# untitled.net
KiCad netlist of a schematic drawn in EAGLE
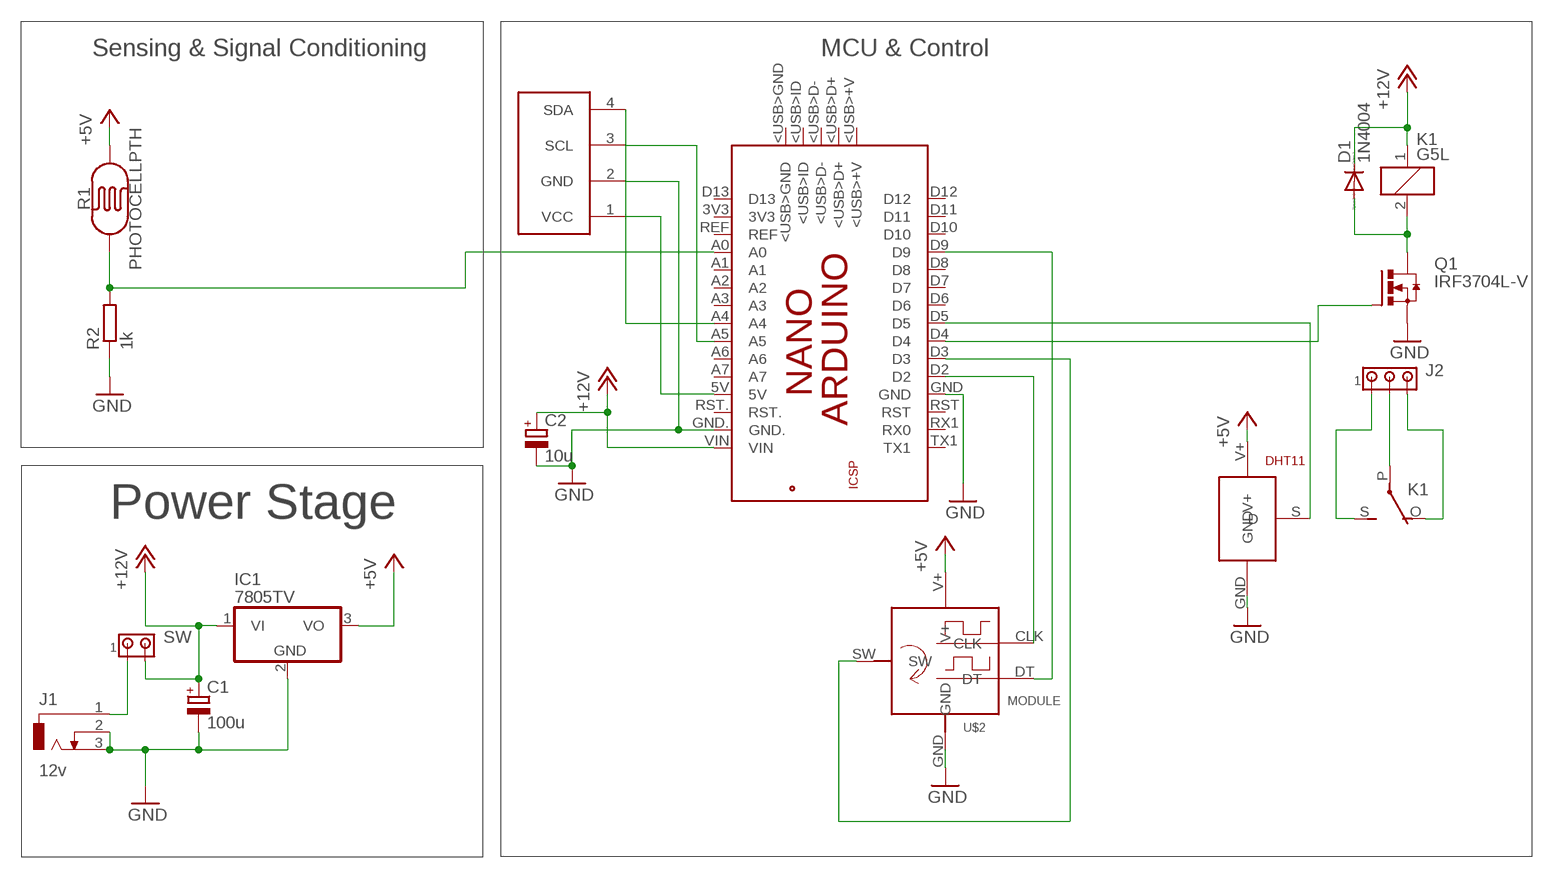
[diagram p0: schematic, sheet 1]

(export (version "E")
  (design (tool "Eeschema 10.0.6"))
  (components
    (comp (ref "C1")
      (value "100u")
      (footprint "eagle-import:E3,5-8")
      (libsource (lib "eagle-import") (part "CPOL-EUE3.5-8"))
    )
    (comp (ref "C2")
      (value "10u")
      (footprint "eagle-import:E3,5-8")
      (libsource (lib "eagle-import") (part "CPOL-EUE3.5-8"))
    )
    (comp (ref "D1")
      (value "1N4004")
      (footprint "eagle-import:DO41-10")
      (fields (field (name "SPICEPREFIX") "D"))
      (libsource (lib "eagle-import") (part "1N4004"))
    )
    (comp (ref "DHT11")
      (value "DHT11")
      (footprint "eagle-import:DHT11")
      (libsource (lib "eagle-import") (part "DHT11"))
    )
    (comp (ref "IC1")
      (value "7805TV")
      (footprint "eagle-import:TO220V")
      (libsource (lib "eagle-import") (part "78TV05"))
    )
    (comp (ref "J1")
      (value "12v")
      (footprint "eagle-import:DCJ0303")
      (libsource (lib "eagle-import") (part "DCJ0303"))
    )
    (comp (ref "J2")
      (value "MTA03-156")
      (footprint "eagle-import:1X3MTA")
      (libsource (lib "eagle-import") (part "MTA03-156"))
    )
    (comp (ref "K1")
      (value "G5L")
      (footprint "eagle-import:G5LE")
      (fields (field (name "SPICEPREFIX") "B"))
      (libsource (lib "eagle-import") (part "G5L"))
    )
    (comp (ref "PCB1")
      (value "ARDUINO_NANO")
      (footprint "eagle-import:ARDUINO_NANO")
      (libsource (lib "eagle-import") (part "ARDUINO_NANO"))
    )
    (comp (ref "Q1")
      (value "IRF3704L-V")
      (footprint "eagle-import:TO262-V")
      (fields (field (name "SPICEPREFIX") "Q"))
      (libsource (lib "eagle-import") (part "IRF3704L-V"))
    )
    (comp (ref "R1")
      (value "PHOTOCELLPTH")
      (footprint "eagle-import:PHOTOCELL")
      (libsource (lib "eagle-import") (part "PHOTOCELLPTH"))
    )
    (comp (ref "R2")
      (value "1k")
      (footprint "eagle-import:0207_7")
      (libsource (lib "eagle-import") (part "R-EU_0207/7"))
    )
    (comp (ref "SW")
      (value "MTA02-156")
      (footprint "eagle-import:1X2MTA")
      (libsource (lib "eagle-import") (part "MTA02-156"))
    )
    (comp (ref "U$1")
      (value "I2C_OLED")
      (footprint "eagle-import:I2C_OLED_PACKAGE")
      (libsource (lib "eagle-import") (part "I2C_OLED"))
    )
    (comp (ref "U$2")
      (value "MODULE")
      (footprint "eagle-import:MODULE_SHEILD")
      (libsource (lib "eagle-import") (part "MODULE"))
    )
  )
  (nets
    (net (code "1") (name "+5V") (class "Default")
      (node (ref "DHT11") (pin "V+") (pinfunction "V+_V+") (pintype "power_in"))
      (node (ref "IC1") (pin "3") (pinfunction "VO_3") (pintype "passive"))
      (node (ref "R1") (pin "2") (pinfunction "P$2_2") (pintype "bidirectional"))
      (node (ref "U$2") (pin "V+") (pinfunction "V+_V+") (pintype "power_in"))
    )
    (net (code "2") (name "+12V") (class "Default")
      (node (ref "C1") (pin "+") (pinfunction "+_+") (pintype "passive"))
      (node (ref "C2") (pin "+") (pinfunction "+_+") (pintype "passive"))
      (node (ref "D1") (pin "C") (pinfunction "C_C") (pintype "passive"))
      (node (ref "IC1") (pin "1") (pinfunction "VI_1") (pintype "input"))
      (node (ref "K1") (pin "1") (pinfunction "1_1") (pintype "passive"))
      (node (ref "PCB1") (pin "VIN") (pinfunction "VIN_VIN") (pintype "bidirectional"))
      (node (ref "SW") (pin "2") (pinfunction "2_2") (pintype "passive"))
    )
    (net (code "3") (name "GND") (class "Default")
      (node (ref "C1") (pin "-") (pinfunction "-_-") (pintype "passive"))
      (node (ref "C2") (pin "-") (pinfunction "-_-") (pintype "passive"))
      (node (ref "DHT11") (pin "GND") (pinfunction "GND_GND") (pintype "power_in"))
      (node (ref "IC1") (pin "2") (pinfunction "GND_2") (pintype "passive"))
      (node (ref "J1") (pin "2") (pinfunction "2_2") (pintype "passive"))
      (node (ref "J1") (pin "3") (pinfunction "3_3") (pintype "passive"))
      (node (ref "PCB1") (pin "GND") (pinfunction "GND_GND") (pintype "bidirectional"))
      (node (ref "PCB1") (pin "GND.") (pinfunction "GND._GND.") (pintype "bidirectional"))
      (node (ref "Q1") (pin "3") (pinfunction "S_3") (pintype "passive"))
      (node (ref "R2") (pin "1") (pinfunction "1_1") (pintype "passive"))
      (node (ref "U$1") (pin "2") (pinfunction "GND_2") (pintype "bidirectional"))
      (node (ref "U$2") (pin "GND") (pinfunction "GND_GND") (pintype "power_in"))
    )
    (net (code "4") (name "Net-(DHT11-D)") (class "Default")
      (node (ref "DHT11") (pin "S") (pinfunction "D_S") (pintype "bidirectional"))
      (node (ref "PCB1") (pin "D5") (pinfunction "D5_D5") (pintype "bidirectional"))
    )
    (net (code "5") (name "Net-(J1-Pad1)") (class "Default")
      (node (ref "J1") (pin "1") (pinfunction "1_1") (pintype "passive"))
      (node (ref "SW") (pin "1") (pinfunction "1_1") (pintype "passive"))
    )
    (net (code "6") (name "Net-(J2-Pad1)") (class "Default")
      (node (ref "J2") (pin "1") (pinfunction "1_1") (pintype "passive"))
      (node (ref "K1") (pin "S") (pinfunction "S_S") (pintype "passive"))
    )
    (net (code "7") (name "Net-(J2-Pad2)") (class "Default")
      (node (ref "J2") (pin "2") (pinfunction "2_2") (pintype "passive"))
      (node (ref "K1") (pin "P") (pinfunction "P_P") (pintype "passive"))
    )
    (net (code "8") (name "Net-(J2-Pad3)") (class "Default")
      (node (ref "J2") (pin "3") (pinfunction "3_3") (pintype "passive"))
      (node (ref "K1") (pin "O") (pinfunction "O_O") (pintype "passive"))
    )
    (net (code "9") (name "Net-(PCB1-PadD2)") (class "Default")
      (node (ref "PCB1") (pin "D2") (pinfunction "D2_D2") (pintype "bidirectional"))
      (node (ref "U$2") (pin "CLK") (pinfunction "CLK_CLK") (pintype "bidirectional"))
    )
    (net (code "10") (name "Net-(PCB1-PadD3)") (class "Default")
      (node (ref "PCB1") (pin "D3") (pinfunction "D3_D3") (pintype "bidirectional"))
      (node (ref "U$2") (pin "SW") (pinfunction "SW_SW") (pintype "bidirectional"))
    )
    (net (code "11") (name "Net-(PCB1-PadD9)") (class "Default")
      (node (ref "PCB1") (pin "D9") (pinfunction "D9_D9") (pintype "bidirectional"))
      (node (ref "U$2") (pin "DT") (pinfunction "DT_DT") (pintype "bidirectional"))
    )
    (net (code "12") (name "Net-(Q1-D)") (class "Default")
      (node (ref "D1") (pin "A") (pinfunction "A_A") (pintype "passive"))
      (node (ref "K1") (pin "2") (pinfunction "2_2") (pintype "passive"))
      (node (ref "Q1") (pin "2") (pinfunction "D_2") (pintype "passive"))
    )
    (net (code "13") (name "Net-(Q1-G)") (class "Default")
      (node (ref "PCB1") (pin "D4") (pinfunction "D4_D4") (pintype "bidirectional"))
      (node (ref "Q1") (pin "1") (pinfunction "G_1") (pintype "passive"))
    )
    (net (code "14") (name "Net-(R1-P$1)") (class "Default")
      (node (ref "PCB1") (pin "A0") (pinfunction "A0_A0") (pintype "bidirectional"))
      (node (ref "R1") (pin "1") (pinfunction "P$1_1") (pintype "bidirectional"))
      (node (ref "R2") (pin "2") (pinfunction "2_2") (pintype "passive"))
    )
    (net (code "15") (name "Net-(U$1-SCL)") (class "Default")
      (node (ref "PCB1") (pin "A5") (pinfunction "A5_A5") (pintype "bidirectional"))
      (node (ref "U$1") (pin "3") (pinfunction "SCL_3") (pintype "bidirectional"))
    )
    (net (code "16") (name "Net-(U$1-SDA)") (class "Default")
      (node (ref "PCB1") (pin "A4") (pinfunction "A4_A4") (pintype "bidirectional"))
      (node (ref "U$1") (pin "4") (pinfunction "SDA_4") (pintype "bidirectional"))
    )
    (net (code "17") (name "Net-(U$1-VCC)") (class "Default")
      (node (ref "PCB1") (pin "5V") (pinfunction "5V_5V") (pintype "bidirectional"))
      (node (ref "U$1") (pin "1") (pinfunction "VCC_1") (pintype "bidirectional"))
    )
    (net (code "18") (name "unconnected-(PCB1-Pad3V3)") (class "Default")
      (node (ref "PCB1") (pin "3V3") (pinfunction "3V3_3V3") (pintype "bidirectional"))
    )
    (net (code "19") (name "unconnected-(PCB1-Pad5V.)") (class "Default")
      (node (ref "PCB1") (pin "5V.") (pinfunction "5V._5V.") (pintype "bidirectional"))
    )
    (net (code "20") (name "unconnected-(PCB1-Pad<USB>+V)") (class "Default")
      (node (ref "PCB1") (pin "<USB>+V") (pinfunction "<USB>+V_<USB>+V") (pintype "bidirectional"))
    )
    (net (code "21") (name "unconnected-(PCB1-Pad<USB>D+)") (class "Default")
      (node (ref "PCB1") (pin "<USB>D+") (pinfunction "<USB>D+_<USB>D+") (pintype "bidirectional"))
    )
    (net (code "22") (name "unconnected-(PCB1-Pad<USB>D-)") (class "Default")
      (node (ref "PCB1") (pin "<USB>D-") (pinfunction "<USB>D-_<USB>D-") (pintype "bidirectional"))
    )
    (net (code "23") (name "unconnected-(PCB1-Pad<USB>GND)") (class "Default")
      (node (ref "PCB1") (pin "<USB>GND") (pinfunction "<USB>GND_<USB>GND") (pintype "bidirectional"))
    )
    (net (code "24") (name "unconnected-(PCB1-Pad<USB>ID)") (class "Default")
      (node (ref "PCB1") (pin "<USB>ID") (pinfunction "<USB>ID_<USB>ID") (pintype "bidirectional"))
    )
    (net (code "25") (name "unconnected-(PCB1-PadA1)") (class "Default")
      (node (ref "PCB1") (pin "A1") (pinfunction "A1_A1") (pintype "bidirectional"))
    )
    (net (code "26") (name "unconnected-(PCB1-PadA2)") (class "Default")
      (node (ref "PCB1") (pin "A2") (pinfunction "A2_A2") (pintype "bidirectional"))
    )
    (net (code "27") (name "unconnected-(PCB1-PadA3)") (class "Default")
      (node (ref "PCB1") (pin "A3") (pinfunction "A3_A3") (pintype "bidirectional"))
    )
    (net (code "28") (name "unconnected-(PCB1-PadA6)") (class "Default")
      (node (ref "PCB1") (pin "A6") (pinfunction "A6_A6") (pintype "bidirectional"))
    )
    (net (code "29") (name "unconnected-(PCB1-PadA7)") (class "Default")
      (node (ref "PCB1") (pin "A7") (pinfunction "A7_A7") (pintype "bidirectional"))
    )
    (net (code "30") (name "unconnected-(PCB1-PadD6)") (class "Default")
      (node (ref "PCB1") (pin "D6") (pinfunction "D6_D6") (pintype "bidirectional"))
    )
    (net (code "31") (name "unconnected-(PCB1-PadD7)") (class "Default")
      (node (ref "PCB1") (pin "D7") (pinfunction "D7_D7") (pintype "bidirectional"))
    )
    (net (code "32") (name "unconnected-(PCB1-PadD8)") (class "Default")
      (node (ref "PCB1") (pin "D8") (pinfunction "D8_D8") (pintype "bidirectional"))
    )
    (net (code "33") (name "unconnected-(PCB1-PadD10)") (class "Default")
      (node (ref "PCB1") (pin "D10") (pinfunction "D10_D10") (pintype "bidirectional"))
    )
    (net (code "34") (name "unconnected-(PCB1-PadD11)") (class "Default")
      (node (ref "PCB1") (pin "D11") (pinfunction "D11_D11") (pintype "bidirectional"))
    )
    (net (code "35") (name "unconnected-(PCB1-PadD12)") (class "Default")
      (node (ref "PCB1") (pin "D12") (pinfunction "D12_D12") (pintype "bidirectional"))
    )
    (net (code "36") (name "unconnected-(PCB1-PadD13)") (class "Default")
      (node (ref "PCB1") (pin "D13") (pinfunction "D13_D13") (pintype "bidirectional"))
    )
    (net (code "37") (name "unconnected-(PCB1-PadGND_)") (class "Default")
      (node (ref "PCB1") (pin "GND_") (pinfunction "GND__GND_") (pintype "bidirectional"))
    )
    (net (code "38") (name "unconnected-(PCB1-PadMISO)") (class "Default")
      (node (ref "PCB1") (pin "MISO") (pinfunction "MISO_MISO") (pintype "bidirectional"))
    )
    (net (code "39") (name "unconnected-(PCB1-PadMOSI)") (class "Default")
      (node (ref "PCB1") (pin "MOSI") (pinfunction "MOSI_MOSI") (pintype "bidirectional"))
    )
    (net (code "40") (name "unconnected-(PCB1-PadREF)") (class "Default")
      (node (ref "PCB1") (pin "REF") (pinfunction "REF_REF") (pintype "bidirectional"))
    )
    (net (code "41") (name "unconnected-(PCB1-PadRESET..)") (class "Default")
      (node (ref "PCB1") (pin "RESET..") (pinfunction "RESET.._RESET..") (pintype "bidirectional"))
    )
    (net (code "42") (name "unconnected-(PCB1-PadRST)") (class "Default")
      (node (ref "PCB1") (pin "RST") (pinfunction "RST_RST") (pintype "bidirectional"))
    )
    (net (code "43") (name "unconnected-(PCB1-PadRST.)") (class "Default")
      (node (ref "PCB1") (pin "RST.") (pinfunction "RST._RST.") (pintype "bidirectional"))
    )
    (net (code "44") (name "unconnected-(PCB1-PadSCK)") (class "Default")
      (node (ref "PCB1") (pin "SCK") (pinfunction "SCK_SCK") (pintype "bidirectional"))
    )
    (net (code "45") (name "unconnected-(PCB1-PadTX1)") (class "Default")
      (node (ref "PCB1") (pin "TX1") (pinfunction "TX1_TX1") (pintype "bidirectional"))
    )
    (net (code "46") (name "unconnected-(PCB1-RX0-PadRX1)") (class "Default")
      (node (ref "PCB1") (pin "RX1") (pinfunction "RX0_RX1") (pintype "bidirectional"))
    )
  )
)
